# Power_Meter_v1_0.net
KiCad netlist of a schematic drawn in EAGLE
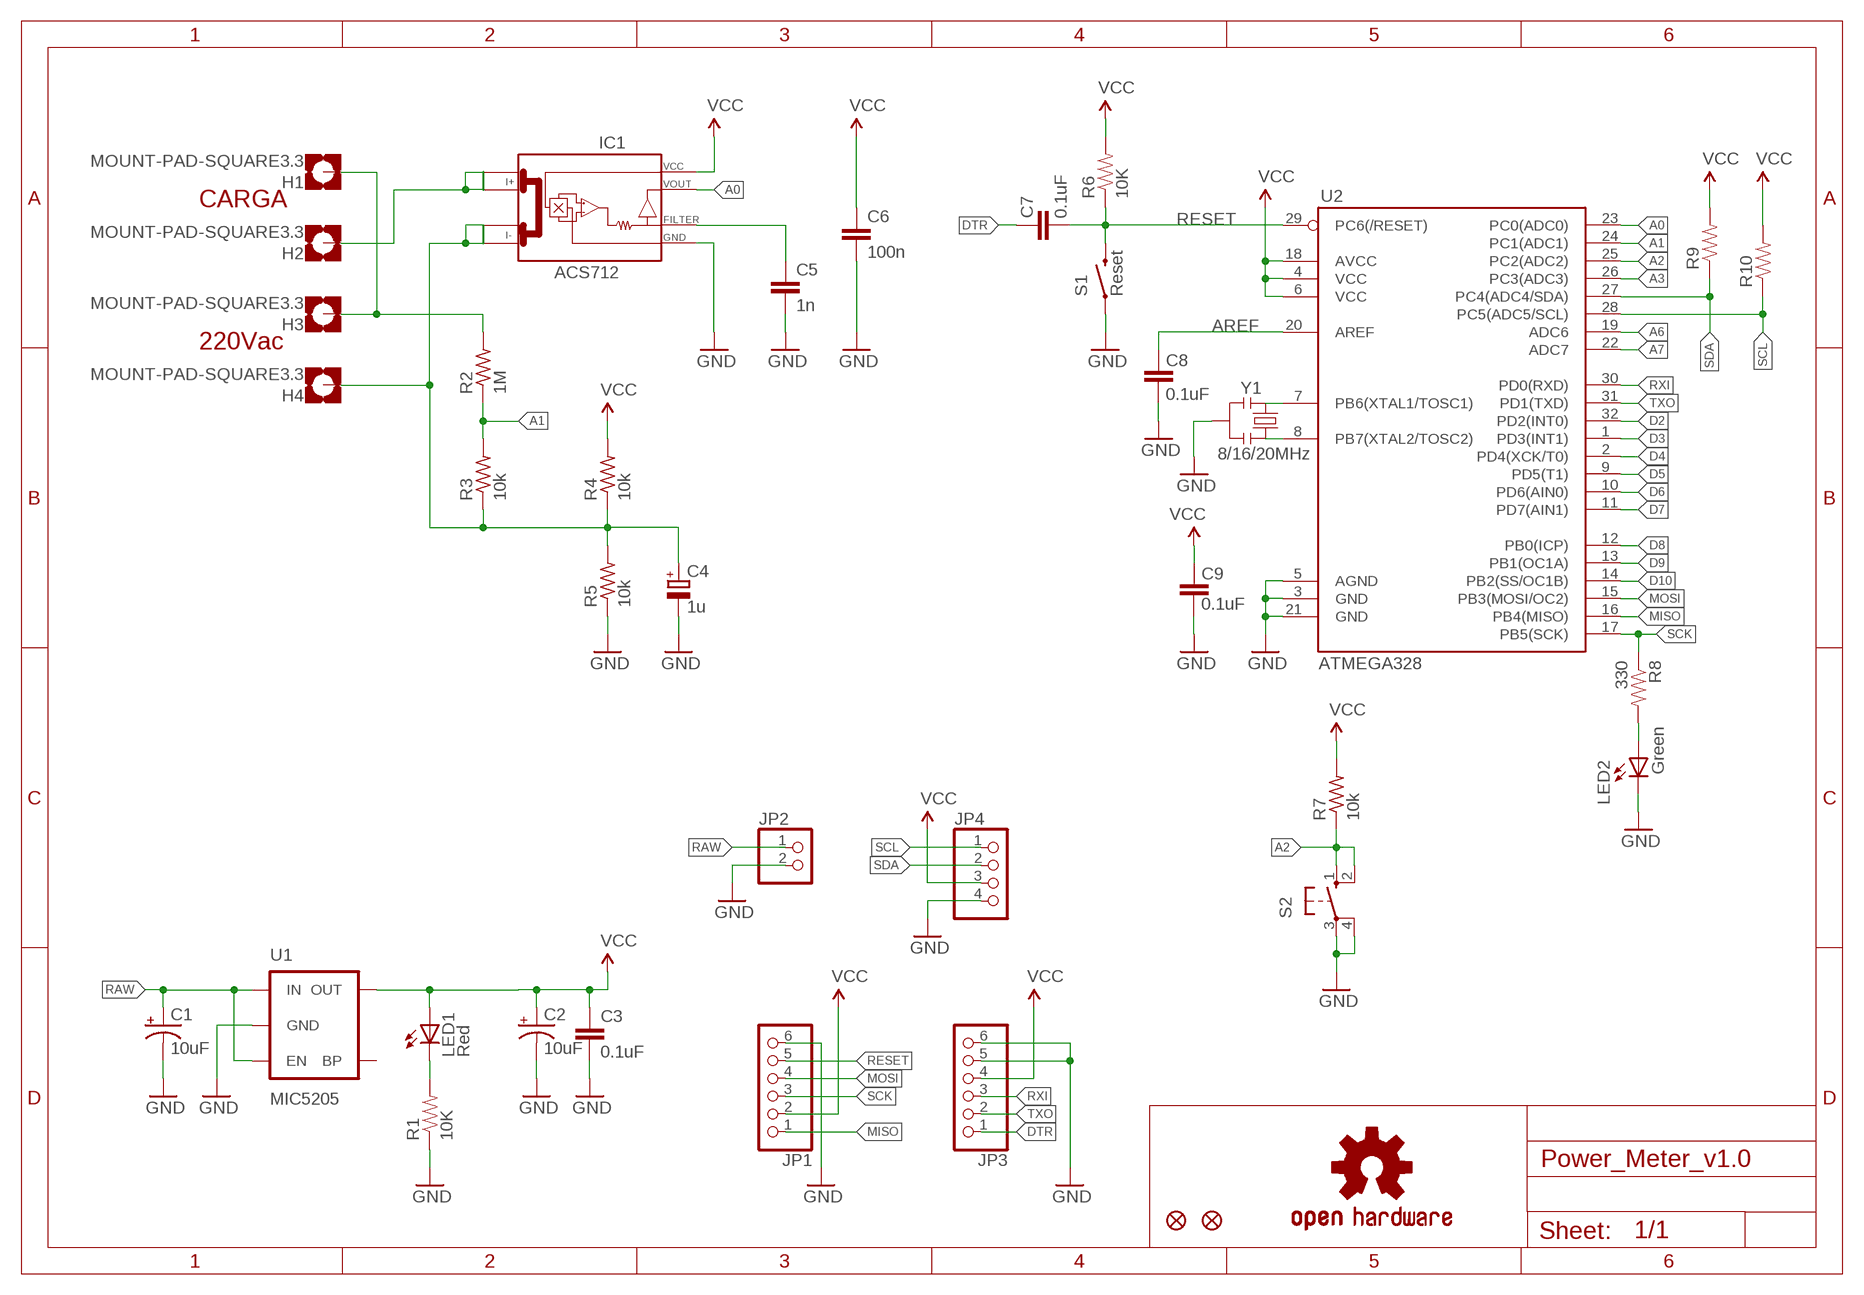
[diagram p0: schematic, sheet 1]

(export (version "E")
  (design (tool "Eeschema 10.0.6"))
  (components
    (comp (ref "C1")
      (value "10uF")
      (footprint "eagle-import:EIA3216")
      (libsource (lib "eagle-import") (part "CAP_POL1206"))
    )
    (comp (ref "C2")
      (value "10uF")
      (footprint "eagle-import:EIA3216")
      (libsource (lib "eagle-import") (part "CAP_POL1206"))
    )
    (comp (ref "C3")
      (value "0.1uF")
      (footprint "eagle-import:0603-CAP")
      (libsource (lib "eagle-import") (part "CAP0603-CAP"))
    )
    (comp (ref "C4")
      (value "1u")
      (footprint "eagle-import:E2-5")
      (libsource (lib "eagle-import") (part "CPOL-EUE2-5"))
    )
    (comp (ref "C5")
      (value "1n")
      (footprint "eagle-import:C0805K")
      (libsource (lib "eagle-import") (part "C-EUC0805K"))
    )
    (comp (ref "C6")
      (value "100n")
      (footprint "eagle-import:C0805K")
      (libsource (lib "eagle-import") (part "C-EUC0805K"))
    )
    (comp (ref "C7")
      (value "0.1uF")
      (footprint "eagle-import:0603-CAP")
      (libsource (lib "eagle-import") (part "CAP0603-CAP"))
    )
    (comp (ref "C8")
      (value "0.1uF")
      (footprint "eagle-import:0603-CAP")
      (libsource (lib "eagle-import") (part "CAP0603-CAP"))
    )
    (comp (ref "C9")
      (value "0.1uF")
      (footprint "eagle-import:0603-CAP")
      (libsource (lib "eagle-import") (part "CAP0603-CAP"))
    )
    (comp (ref "H1")
      (value "MOUNT-PAD-SQUARE3.3")
      (footprint "eagle-import:3,3-PAD-SQUARE")
      (libsource (lib "eagle-import") (part "MOUNT-PAD-SQUARE3.3"))
    )
    (comp (ref "H2")
      (value "MOUNT-PAD-SQUARE3.3")
      (footprint "eagle-import:3,3-PAD-SQUARE")
      (libsource (lib "eagle-import") (part "MOUNT-PAD-SQUARE3.3"))
    )
    (comp (ref "H3")
      (value "MOUNT-PAD-SQUARE3.3")
      (footprint "eagle-import:3,3-PAD-SQUARE")
      (libsource (lib "eagle-import") (part "MOUNT-PAD-SQUARE3.3"))
    )
    (comp (ref "H4")
      (value "MOUNT-PAD-SQUARE3.3")
      (footprint "eagle-import:3,3-PAD-SQUARE")
      (libsource (lib "eagle-import") (part "MOUNT-PAD-SQUARE3.3"))
    )
    (comp (ref "IC1")
      (value "ACS712")
      (footprint "eagle-import:SO08")
      (libsource (lib "eagle-import") (part "ACS712"))
    )
    (comp (ref "JP1")
      (value "PINHD-1X6")
      (footprint "eagle-import:1X06")
      (libsource (lib "eagle-import") (part "PINHD-1X6"))
    )
    (comp (ref "JP2")
      (value "PINHD-1X2")
      (footprint "eagle-import:1X02")
      (libsource (lib "eagle-import") (part "PINHD-1X2"))
    )
    (comp (ref "JP3")
      (value "PINHD-1X6")
      (footprint "eagle-import:1X06")
      (libsource (lib "eagle-import") (part "PINHD-1X6"))
    )
    (comp (ref "JP4")
      (value "PINHD-1X4")
      (footprint "eagle-import:1X04")
      (libsource (lib "eagle-import") (part "PINHD-1X4"))
    )
    (comp (ref "JP5")
      (value "FIDUCIAL1X2.5")
      (footprint "eagle-import:FIDUCIAL-1X2.5")
      (libsource (lib "eagle-import") (part "FIDUCIAL1X2.5"))
    )
    (comp (ref "JP6")
      (value "FIDUCIAL1X2.5")
      (footprint "eagle-import:FIDUCIAL-1X2.5")
      (libsource (lib "eagle-import") (part "FIDUCIAL1X2.5"))
    )
    (comp (ref "LED1")
      (value "Red")
      (footprint "eagle-import:0603-LED-ALT1")
      (libsource (lib "eagle-import") (part "LED"))
    )
    (comp (ref "LED2")
      (value "Green")
      (footprint "eagle-import:0603-LED-ALT1")
      (libsource (lib "eagle-import") (part "LED"))
    )
    (comp (ref "R1")
      (value "10K")
      (footprint "eagle-import:0603-RES")
      (libsource (lib "eagle-import") (part "RESISTOR0603-RES"))
    )
    (comp (ref "R2")
      (value "1M")
      (footprint "eagle-import:0204_7")
      (libsource (lib "eagle-import") (part "R-US_0204/7"))
    )
    (comp (ref "R3")
      (value "10k")
      (footprint "eagle-import:0204_7")
      (libsource (lib "eagle-import") (part "R-US_0204/7"))
    )
    (comp (ref "R4")
      (value "10k")
      (footprint "eagle-import:0204_7")
      (libsource (lib "eagle-import") (part "R-US_0204/7"))
    )
    (comp (ref "R5")
      (value "10k")
      (footprint "eagle-import:0204_7")
      (libsource (lib "eagle-import") (part "R-US_0204/7"))
    )
    (comp (ref "R6")
      (value "10K")
      (footprint "eagle-import:0603-RES")
      (libsource (lib "eagle-import") (part "RESISTOR0603-RES"))
    )
    (comp (ref "R7")
      (value "10k")
      (footprint "eagle-import:0204_7")
      (libsource (lib "eagle-import") (part "R-US_0204/7"))
    )
    (comp (ref "R8")
      (value "330")
      (footprint "eagle-import:0603-RES")
      (libsource (lib "eagle-import") (part "RESISTOR0603-RES"))
    )
    (comp (ref "R9")
      (value "RESISTOR0603-RES")
      (footprint "eagle-import:0603-RES")
      (libsource (lib "eagle-import") (part "RESISTOR0603-RES"))
    )
    (comp (ref "R10")
      (value "RESISTOR0603-RES")
      (footprint "eagle-import:0603-RES")
      (libsource (lib "eagle-import") (part "RESISTOR0603-RES"))
    )
    (comp (ref "S1")
      (value "Reset")
      (footprint "eagle-import:TACTILE-SWITCH-SMD-ALT01")
      (libsource (lib "eagle-import") (part "SWITCH-MOMENTARY-2SMD-ALT01"))
    )
    (comp (ref "S2")
      (value "10-XX")
      (footprint "eagle-import:B3F-10XX")
      (fields (field (name "MPN") "B3F-1000"))
      (libsource (lib "eagle-import") (part "10-XX"))
    )
    (comp (ref "U$5")
      (value "OSHW-LOGOS")
      (footprint "eagle-import:OSHW-LOGO-S")
      (libsource (lib "eagle-import") (part "OSHW-LOGOS"))
    )
    (comp (ref "U1")
      (value "MIC5205")
      (footprint "eagle-import:SOT23-5")
      (libsource (lib "eagle-import") (part "V_REG_LDOSMD"))
    )
    (comp (ref "U2")
      (value "ATMEGA328")
      (footprint "eagle-import:TQFP32-08")
      (libsource (lib "eagle-import") (part "ATMEGA168"))
    )
    (comp (ref "Y1")
      (value "8/16/20MHz")
      (footprint "eagle-import:RESONATOR-SMD-1_1")
      (libsource (lib "eagle-import") (part "RESONATOR1{colon}1"))
    )
  )
  (nets
    (net (code "1") (name "/AREF") (class "Default")
      (node (ref "C8") (pin "2") (pinfunction "2_2") (pintype "passive"))
      (node (ref "U2") (pin "20") (pinfunction "AREF_20") (pintype "bidirectional"))
    )
    (net (code "2") (name "A0") (class "Default")
      (node (ref "IC1") (pin "7") (pinfunction "VOUT_7") (pintype "output"))
      (node (ref "U2") (pin "23") (pinfunction "PC0(ADC0)_23") (pintype "bidirectional"))
    )
    (net (code "3") (name "A1") (class "Default")
      (node (ref "R2") (pin "1") (pinfunction "1_1") (pintype "passive"))
      (node (ref "R3") (pin "2") (pinfunction "2_2") (pintype "passive"))
      (node (ref "U2") (pin "24") (pinfunction "PC1(ADC1)_24") (pintype "bidirectional"))
    )
    (net (code "4") (name "A2") (class "Default")
      (node (ref "R7") (pin "1") (pinfunction "1_1") (pintype "passive"))
      (node (ref "S2") (pin "1") (pinfunction "S_1") (pintype "passive"))
      (node (ref "S2") (pin "2") (pinfunction "S1_2") (pintype "passive"))
      (node (ref "U2") (pin "25") (pinfunction "PC2(ADC2)_25") (pintype "bidirectional"))
    )
    (net (code "5") (name "A3") (class "Default")
      (node (ref "U2") (pin "26") (pinfunction "PC3(ADC3)_26") (pintype "bidirectional"))
    )
    (net (code "6") (name "A6") (class "Default")
      (node (ref "U2") (pin "19") (pinfunction "ADC6_19") (pintype "bidirectional"))
    )
    (net (code "7") (name "A7") (class "Default")
      (node (ref "U2") (pin "22") (pinfunction "ADC7_22") (pintype "bidirectional"))
    )
    (net (code "8") (name "D2") (class "Default")
      (node (ref "U2") (pin "32") (pinfunction "PD2(INT0)_32") (pintype "bidirectional"))
    )
    (net (code "9") (name "D3") (class "Default")
      (node (ref "U2") (pin "1") (pinfunction "PD3(INT1)_1") (pintype "bidirectional"))
    )
    (net (code "10") (name "D4") (class "Default")
      (node (ref "U2") (pin "2") (pinfunction "PD4(XCK/T0)_2") (pintype "bidirectional"))
    )
    (net (code "11") (name "D5") (class "Default")
      (node (ref "U2") (pin "9") (pinfunction "PD5(T1)_9") (pintype "bidirectional"))
    )
    (net (code "12") (name "D6") (class "Default")
      (node (ref "U2") (pin "10") (pinfunction "PD6(AIN0)_10") (pintype "bidirectional"))
    )
    (net (code "13") (name "D7") (class "Default")
      (node (ref "U2") (pin "11") (pinfunction "PD7(AIN1)_11") (pintype "bidirectional"))
    )
    (net (code "14") (name "D8") (class "Default")
      (node (ref "U2") (pin "12") (pinfunction "PB0(ICP)_12") (pintype "bidirectional"))
    )
    (net (code "15") (name "D9") (class "Default")
      (node (ref "U2") (pin "13") (pinfunction "PB1(OC1A)_13") (pintype "bidirectional"))
    )
    (net (code "16") (name "D10") (class "Default")
      (node (ref "U2") (pin "14") (pinfunction "PB2(SS/OC1B)_14") (pintype "bidirectional"))
    )
    (net (code "17") (name "DTR") (class "Default")
      (node (ref "C7") (pin "2") (pinfunction "2_2") (pintype "passive"))
      (node (ref "JP3") (pin "1") (pinfunction "1_1") (pintype "passive"))
    )
    (net (code "18") (name "GND") (class "Default")
      (node (ref "C1") (pin "C") (pinfunction "-_C") (pintype "passive"))
      (node (ref "C2") (pin "C") (pinfunction "-_C") (pintype "passive"))
      (node (ref "C3") (pin "2") (pinfunction "2_2") (pintype "passive"))
      (node (ref "C4") (pin "-") (pinfunction "-_-") (pintype "passive"))
      (node (ref "C5") (pin "2") (pinfunction "2_2") (pintype "passive"))
      (node (ref "C6") (pin "2") (pinfunction "2_2") (pintype "passive"))
      (node (ref "C8") (pin "1") (pinfunction "1_1") (pintype "passive"))
      (node (ref "C9") (pin "1") (pinfunction "1_1") (pintype "passive"))
      (node (ref "IC1") (pin "5") (pinfunction "GND_5") (pintype "power_in"))
      (node (ref "JP1") (pin "6") (pinfunction "6_6") (pintype "passive"))
      (node (ref "JP2") (pin "2") (pinfunction "2_2") (pintype "passive"))
      (node (ref "JP3") (pin "5") (pinfunction "5_5") (pintype "passive"))
      (node (ref "JP3") (pin "6") (pinfunction "6_6") (pintype "passive"))
      (node (ref "JP4") (pin "4") (pinfunction "4_4") (pintype "passive"))
      (node (ref "LED2") (pin "C") (pinfunction "C_C") (pintype "passive"))
      (node (ref "R1") (pin "1") (pinfunction "1_1") (pintype "passive"))
      (node (ref "R5") (pin "1") (pinfunction "1_1") (pintype "passive"))
      (node (ref "S1") (pin "1") (pinfunction "1_1") (pintype "passive"))
      (node (ref "S1") (pin "2") (pinfunction "1_2") (pintype "passive"))
      (node (ref "S2") (pin "3") (pinfunction "P_3") (pintype "passive"))
      (node (ref "S2") (pin "4") (pinfunction "P1_4") (pintype "passive"))
      (node (ref "U1") (pin "2") (pinfunction "GND_2") (pintype "input"))
      (node (ref "U2") (pin "21") (pinfunction "GND_21") (pintype "bidirectional"))
      (node (ref "U2") (pin "3") (pinfunction "GND_3") (pintype "bidirectional"))
      (node (ref "U2") (pin "5") (pinfunction "AGND_5") (pintype "bidirectional"))
      (node (ref "Y1") (pin "2") (pinfunction "2_2") (pintype "passive"))
    )
    (net (code "19") (name "MISO") (class "Default")
      (node (ref "JP1") (pin "1") (pinfunction "1_1") (pintype "passive"))
      (node (ref "U2") (pin "16") (pinfunction "PB4(MISO)_16") (pintype "bidirectional"))
    )
    (net (code "20") (name "MOSI") (class "Default")
      (node (ref "JP1") (pin "4") (pinfunction "4_4") (pintype "passive"))
      (node (ref "U2") (pin "15") (pinfunction "PB3(MOSI/OC2)_15") (pintype "bidirectional"))
    )
    (net (code "21") (name "Net-(H1-MOUNT)") (class "Default")
      (node (ref "H1") (pin "B3,3") (pinfunction "MOUNT_B3,3") (pintype "passive"))
      (node (ref "H3") (pin "B3,3") (pinfunction "MOUNT_B3,3") (pintype "passive"))
      (node (ref "R2") (pin "2") (pinfunction "2_2") (pintype "passive"))
    )
    (net (code "22") (name "Net-(H2-MOUNT)") (class "Default")
      (node (ref "H2") (pin "B3,3") (pinfunction "MOUNT_B3,3") (pintype "passive"))
      (node (ref "IC1") (pin "1") (pinfunction "I+_0_1") (pintype "bidirectional"))
      (node (ref "IC1") (pin "2") (pinfunction "I+_1_2") (pintype "bidirectional"))
    )
    (net (code "23") (name "Net-(H4-MOUNT)") (class "Default")
      (node (ref "C4") (pin "+") (pinfunction "+_+") (pintype "passive"))
      (node (ref "H4") (pin "B3,3") (pinfunction "MOUNT_B3,3") (pintype "passive"))
      (node (ref "IC1") (pin "3") (pinfunction "I-_0_3") (pintype "bidirectional"))
      (node (ref "IC1") (pin "4") (pinfunction "I-_1_4") (pintype "bidirectional"))
      (node (ref "R3") (pin "1") (pinfunction "1_1") (pintype "passive"))
      (node (ref "R4") (pin "1") (pinfunction "1_1") (pintype "passive"))
      (node (ref "R5") (pin "2") (pinfunction "2_2") (pintype "passive"))
    )
    (net (code "24") (name "Net-(IC1-FILTER)") (class "Default")
      (node (ref "C5") (pin "1") (pinfunction "1_1") (pintype "passive"))
      (node (ref "IC1") (pin "6") (pinfunction "FILTER_6") (pintype "bidirectional"))
    )
    (net (code "25") (name "Net-(LED1-PadC)") (class "Default")
      (node (ref "LED1") (pin "C") (pinfunction "C_C") (pintype "passive"))
      (node (ref "R1") (pin "2") (pinfunction "2_2") (pintype "passive"))
    )
    (net (code "26") (name "Net-(LED2-PadA)") (class "Default")
      (node (ref "LED2") (pin "A") (pinfunction "A_A") (pintype "passive"))
      (node (ref "R8") (pin "2") (pinfunction "2_2") (pintype "passive"))
    )
    (net (code "27") (name "Net-(U2-PB6(XTAL1{slash}TOSC1))") (class "Default")
      (node (ref "U2") (pin "7") (pinfunction "PB6(XTAL1/TOSC1)_7") (pintype "bidirectional"))
      (node (ref "Y1") (pin "1") (pinfunction "1_1") (pintype "passive"))
    )
    (net (code "28") (name "Net-(U2-PB7(XTAL2{slash}TOSC2))") (class "Default")
      (node (ref "U2") (pin "8") (pinfunction "PB7(XTAL2/TOSC2)_8") (pintype "bidirectional"))
      (node (ref "Y1") (pin "3") (pinfunction "3_3") (pintype "passive"))
    )
    (net (code "29") (name "RAW") (class "Default")
      (node (ref "C1") (pin "A") (pinfunction "+_A") (pintype "passive"))
      (node (ref "JP2") (pin "1") (pinfunction "1_1") (pintype "passive"))
      (node (ref "U1") (pin "1") (pinfunction "IN_1") (pintype "input"))
      (node (ref "U1") (pin "3") (pinfunction "EN_3") (pintype "input"))
    )
    (net (code "30") (name "RESET") (class "Default")
      (node (ref "C7") (pin "1") (pinfunction "1_1") (pintype "passive"))
      (node (ref "JP1") (pin "5") (pinfunction "5_5") (pintype "passive"))
      (node (ref "R6") (pin "1") (pinfunction "1_1") (pintype "passive"))
      (node (ref "S1") (pin "3") (pinfunction "2_3") (pintype "passive"))
      (node (ref "S1") (pin "4") (pinfunction "2_4") (pintype "passive"))
      (node (ref "U2") (pin "29") (pinfunction "PC6(/RESET)_29") (pintype "bidirectional"))
    )
    (net (code "31") (name "RXI") (class "Default")
      (node (ref "JP3") (pin "3") (pinfunction "3_3") (pintype "passive"))
      (node (ref "U2") (pin "30") (pinfunction "PD0(RXD)_30") (pintype "bidirectional"))
    )
    (net (code "32") (name "SCK") (class "Default")
      (node (ref "JP1") (pin "3") (pinfunction "3_3") (pintype "passive"))
      (node (ref "R8") (pin "1") (pinfunction "1_1") (pintype "passive"))
      (node (ref "U2") (pin "17") (pinfunction "PB5(SCK)_17") (pintype "bidirectional"))
    )
    (net (code "33") (name "SCL") (class "Default")
      (node (ref "JP4") (pin "1") (pinfunction "1_1") (pintype "passive"))
      (node (ref "R10") (pin "1") (pinfunction "1_1") (pintype "passive"))
      (node (ref "U2") (pin "28") (pinfunction "PC5(ADC5/SCL)_28") (pintype "bidirectional"))
    )
    (net (code "34") (name "SDA") (class "Default")
      (node (ref "JP4") (pin "2") (pinfunction "2_2") (pintype "passive"))
      (node (ref "R9") (pin "1") (pinfunction "1_1") (pintype "passive"))
      (node (ref "U2") (pin "27") (pinfunction "PC4(ADC4/SDA)_27") (pintype "bidirectional"))
    )
    (net (code "35") (name "TXO") (class "Default")
      (node (ref "JP3") (pin "2") (pinfunction "2_2") (pintype "passive"))
      (node (ref "U2") (pin "31") (pinfunction "PD1(TXD)_31") (pintype "bidirectional"))
    )
    (net (code "36") (name "VCC") (class "Default")
      (node (ref "C2") (pin "A") (pinfunction "+_A") (pintype "passive"))
      (node (ref "C3") (pin "1") (pinfunction "1_1") (pintype "passive"))
      (node (ref "C6") (pin "1") (pinfunction "1_1") (pintype "passive"))
      (node (ref "C9") (pin "2") (pinfunction "2_2") (pintype "passive"))
      (node (ref "IC1") (pin "8") (pinfunction "VCC_8") (pintype "power_in"))
      (node (ref "JP1") (pin "2") (pinfunction "2_2") (pintype "passive"))
      (node (ref "JP3") (pin "4") (pinfunction "4_4") (pintype "passive"))
      (node (ref "JP4") (pin "3") (pinfunction "3_3") (pintype "passive"))
      (node (ref "LED1") (pin "A") (pinfunction "A_A") (pintype "passive"))
      (node (ref "R10") (pin "2") (pinfunction "2_2") (pintype "passive"))
      (node (ref "R4") (pin "2") (pinfunction "2_2") (pintype "passive"))
      (node (ref "R6") (pin "2") (pinfunction "2_2") (pintype "passive"))
      (node (ref "R7") (pin "2") (pinfunction "2_2") (pintype "passive"))
      (node (ref "R9") (pin "2") (pinfunction "2_2") (pintype "passive"))
      (node (ref "U1") (pin "5") (pinfunction "OUT_5") (pintype "passive"))
      (node (ref "U2") (pin "18") (pinfunction "AVCC_18") (pintype "bidirectional"))
      (node (ref "U2") (pin "4") (pinfunction "VCC_4") (pintype "bidirectional"))
      (node (ref "U2") (pin "6") (pinfunction "VCC_6") (pintype "bidirectional"))
    )
    (net (code "37") (name "unconnected-(U1-BP-Pad4)") (class "Default")
      (node (ref "U1") (pin "4") (pinfunction "BP_4") (pintype "input"))
    )
  )
)
